# Project5.net
KiCad netlist of a schematic drawn in EasyEDA Pro
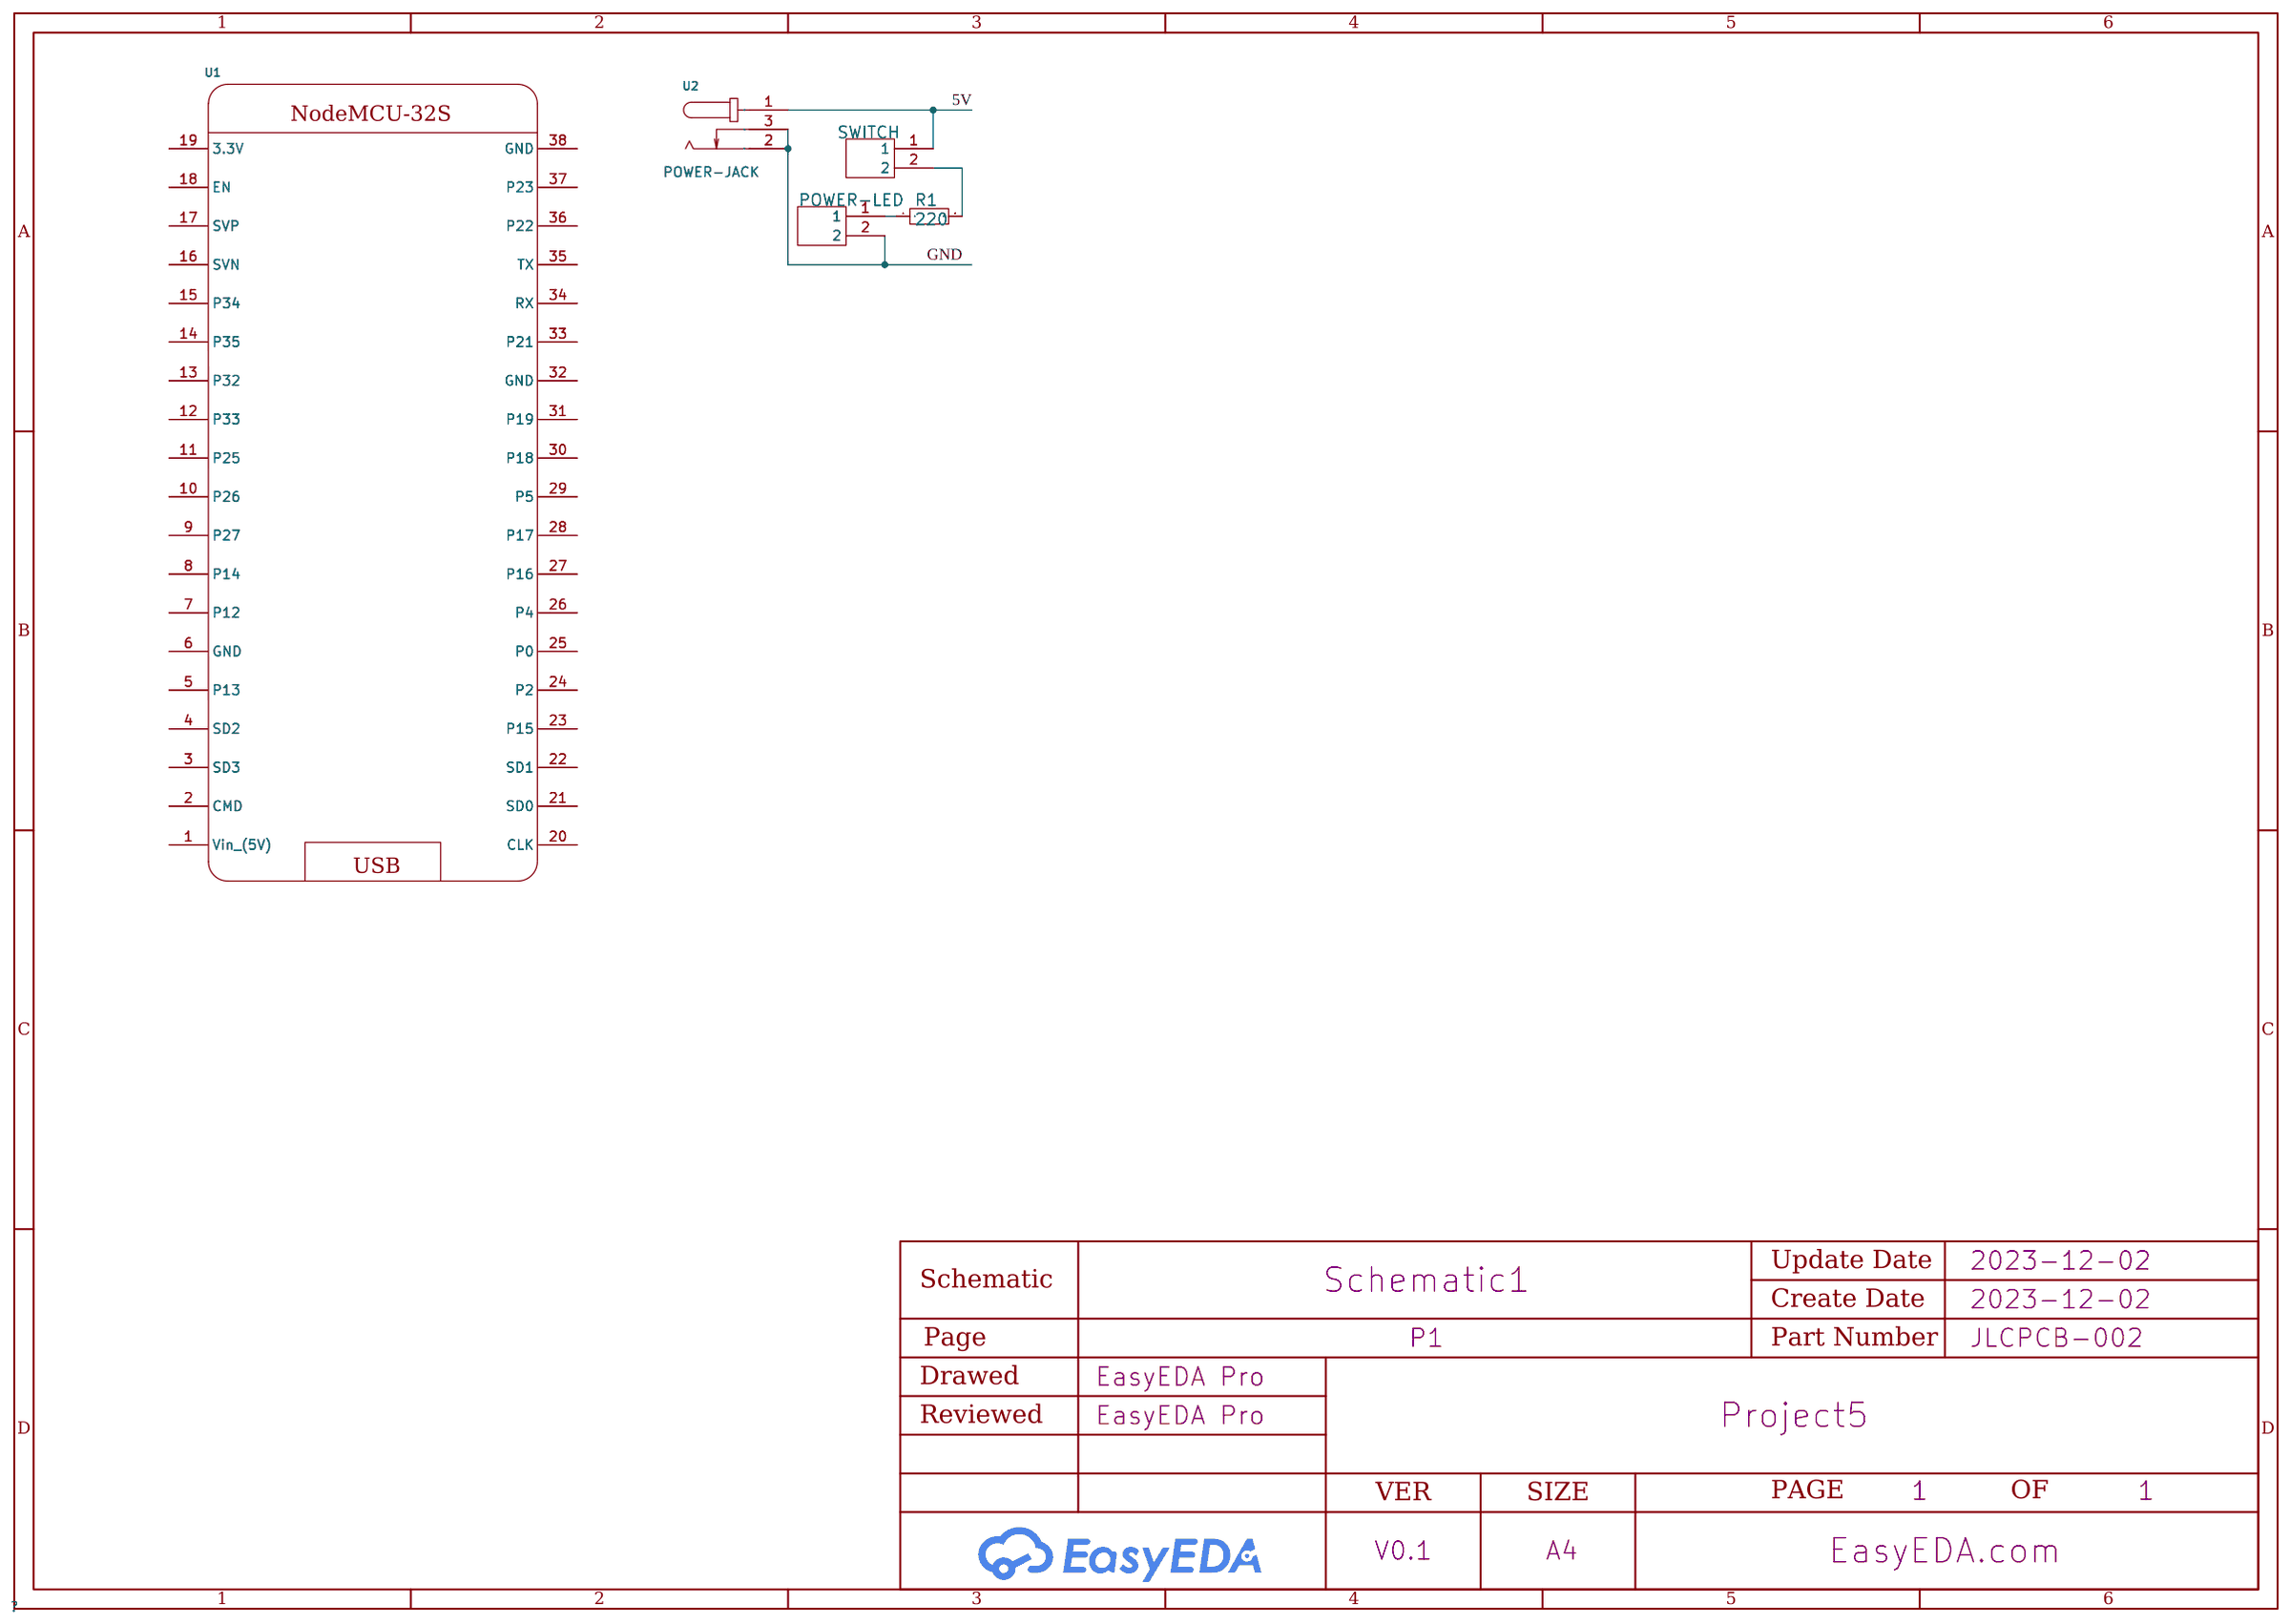
[diagram p0: schematic sheet]

(export (version "E")
  (design (tool "Eeschema 10.0.6"))
  (components
    (comp (ref "POWER-LED")
      (value "~")
      (footprint "easyedapro:JST 2.54-2PIN")
      (libsource (lib "easyedapro") (part "symbol_8d83"))
    )
    (comp (ref "R1")
      (value "220")
      (footprint "easyedapro:RES35")
      (fields
        (field (name "Manufacturer Part") "PTFR0805B130KN9")
        (field (name "Manufacturer") "ResistorToday")
      )
      (libsource (lib "easyedapro") (part "220"))
    )
    (comp (ref "SWITCH")
      (value "~")
      (footprint "easyedapro:JST 2.54-2PIN")
      (libsource (lib "easyedapro") (part "symbol_8d83"))
    )
    (comp (ref "U1")
      (value "~")
      (footprint "easyedapro:AI-THINKER_NODEMCU-32SLUA")
      (libsource (lib "easyedapro") (part "NODEMCU-ESP32"))
    )
    (comp (ref "U2")
      (value "POWER-JACK")
      (footprint "easyedapro:DC-IN-TH_POWER-JACK")
      (libsource (lib "easyedapro") (part "POWER-JACK"))
    )
  )
  (nets
    (net (code "1") (name "/5V") (class "Default")
      (node (ref "SWITCH") (pin "1") (pinfunction "1_1") (pintype "input"))
      (node (ref "U2") (pin "1") (pinfunction "1_1") (pintype "input"))
    )
    (net (code "2") (name "/GND") (class "Default")
      (node (ref "POWER-LED") (pin "2") (pinfunction "2_2") (pintype "input"))
      (node (ref "U2") (pin "2") (pinfunction "2_2") (pintype "input"))
      (node (ref "U2") (pin "3") (pinfunction "3_3") (pintype "input"))
    )
    (net (code "3") (name "Net-(POWER-LED-Pad1)") (class "Default")
      (node (ref "POWER-LED") (pin "1") (pinfunction "1_1") (pintype "input"))
      (node (ref "R1") (pin "1") (pinfunction "1_1") (pintype "input"))
    )
    (net (code "4") (name "Net-(R1-Pad2)") (class "Default")
      (node (ref "R1") (pin "2") (pinfunction "2_2") (pintype "input"))
      (node (ref "SWITCH") (pin "2") (pinfunction "2_2") (pintype "input"))
    )
    (net (code "5") (name "unconnected-(U1-3.3V-Pad19)") (class "Default")
      (node (ref "U1") (pin "19") (pinfunction "3.3V_19") (pintype "input"))
    )
    (net (code "6") (name "unconnected-(U1-CLK-Pad20)") (class "Default")
      (node (ref "U1") (pin "20") (pinfunction "CLK_20") (pintype "input"))
    )
    (net (code "7") (name "unconnected-(U1-CMD-Pad2)") (class "Default")
      (node (ref "U1") (pin "2") (pinfunction "CMD_2") (pintype "input"))
    )
    (net (code "8") (name "unconnected-(U1-EN-Pad18)") (class "Default")
      (node (ref "U1") (pin "18") (pinfunction "EN_18") (pintype "input"))
    )
    (net (code "9") (name "unconnected-(U1-GND-Pad6)") (class "Default")
      (node (ref "U1") (pin "6") (pinfunction "GND_6") (pintype "input"))
    )
    (net (code "10") (name "unconnected-(U1-GND-Pad32)") (class "Default")
      (node (ref "U1") (pin "32") (pinfunction "GND_32") (pintype "input"))
    )
    (net (code "11") (name "unconnected-(U1-GND-Pad38)") (class "Default")
      (node (ref "U1") (pin "38") (pinfunction "GND_38") (pintype "input"))
    )
    (net (code "12") (name "unconnected-(U1-P0-Pad25)") (class "Default")
      (node (ref "U1") (pin "25") (pinfunction "P0_25") (pintype "input"))
    )
    (net (code "13") (name "unconnected-(U1-P2-Pad24)") (class "Default")
      (node (ref "U1") (pin "24") (pinfunction "P2_24") (pintype "input"))
    )
    (net (code "14") (name "unconnected-(U1-P4-Pad26)") (class "Default")
      (node (ref "U1") (pin "26") (pinfunction "P4_26") (pintype "input"))
    )
    (net (code "15") (name "unconnected-(U1-P5-Pad29)") (class "Default")
      (node (ref "U1") (pin "29") (pinfunction "P5_29") (pintype "input"))
    )
    (net (code "16") (name "unconnected-(U1-P12-Pad7)") (class "Default")
      (node (ref "U1") (pin "7") (pinfunction "P12_7") (pintype "input"))
    )
    (net (code "17") (name "unconnected-(U1-P13-Pad5)") (class "Default")
      (node (ref "U1") (pin "5") (pinfunction "P13_5") (pintype "input"))
    )
    (net (code "18") (name "unconnected-(U1-P14-Pad8)") (class "Default")
      (node (ref "U1") (pin "8") (pinfunction "P14_8") (pintype "input"))
    )
    (net (code "19") (name "unconnected-(U1-P15-Pad23)") (class "Default")
      (node (ref "U1") (pin "23") (pinfunction "P15_23") (pintype "input"))
    )
    (net (code "20") (name "unconnected-(U1-P16-Pad27)") (class "Default")
      (node (ref "U1") (pin "27") (pinfunction "P16_27") (pintype "input"))
    )
    (net (code "21") (name "unconnected-(U1-P17-Pad28)") (class "Default")
      (node (ref "U1") (pin "28") (pinfunction "P17_28") (pintype "input"))
    )
    (net (code "22") (name "unconnected-(U1-P18-Pad30)") (class "Default")
      (node (ref "U1") (pin "30") (pinfunction "P18_30") (pintype "input"))
    )
    (net (code "23") (name "unconnected-(U1-P19-Pad31)") (class "Default")
      (node (ref "U1") (pin "31") (pinfunction "P19_31") (pintype "input"))
    )
    (net (code "24") (name "unconnected-(U1-P21-Pad33)") (class "Default")
      (node (ref "U1") (pin "33") (pinfunction "P21_33") (pintype "input"))
    )
    (net (code "25") (name "unconnected-(U1-P22-Pad36)") (class "Default")
      (node (ref "U1") (pin "36") (pinfunction "P22_36") (pintype "input"))
    )
    (net (code "26") (name "unconnected-(U1-P23-Pad37)") (class "Default")
      (node (ref "U1") (pin "37") (pinfunction "P23_37") (pintype "input"))
    )
    (net (code "27") (name "unconnected-(U1-P25-Pad11)") (class "Default")
      (node (ref "U1") (pin "11") (pinfunction "P25_11") (pintype "input"))
    )
    (net (code "28") (name "unconnected-(U1-P26-Pad10)") (class "Default")
      (node (ref "U1") (pin "10") (pinfunction "P26_10") (pintype "input"))
    )
    (net (code "29") (name "unconnected-(U1-P27-Pad9)") (class "Default")
      (node (ref "U1") (pin "9") (pinfunction "P27_9") (pintype "input"))
    )
    (net (code "30") (name "unconnected-(U1-P32-Pad13)") (class "Default")
      (node (ref "U1") (pin "13") (pinfunction "P32_13") (pintype "input"))
    )
    (net (code "31") (name "unconnected-(U1-P33-Pad12)") (class "Default")
      (node (ref "U1") (pin "12") (pinfunction "P33_12") (pintype "input"))
    )
    (net (code "32") (name "unconnected-(U1-P34-Pad15)") (class "Default")
      (node (ref "U1") (pin "15") (pinfunction "P34_15") (pintype "input"))
    )
    (net (code "33") (name "unconnected-(U1-P35-Pad14)") (class "Default")
      (node (ref "U1") (pin "14") (pinfunction "P35_14") (pintype "input"))
    )
    (net (code "34") (name "unconnected-(U1-RX-Pad34)") (class "Default")
      (node (ref "U1") (pin "34") (pinfunction "RX_34") (pintype "input"))
    )
    (net (code "35") (name "unconnected-(U1-SD0-Pad21)") (class "Default")
      (node (ref "U1") (pin "21") (pinfunction "SD0_21") (pintype "input"))
    )
    (net (code "36") (name "unconnected-(U1-SD1-Pad22)") (class "Default")
      (node (ref "U1") (pin "22") (pinfunction "SD1_22") (pintype "input"))
    )
    (net (code "37") (name "unconnected-(U1-SD2-Pad4)") (class "Default")
      (node (ref "U1") (pin "4") (pinfunction "SD2_4") (pintype "input"))
    )
    (net (code "38") (name "unconnected-(U1-SD3-Pad3)") (class "Default")
      (node (ref "U1") (pin "3") (pinfunction "SD3_3") (pintype "input"))
    )
    (net (code "39") (name "unconnected-(U1-SVN-Pad16)") (class "Default")
      (node (ref "U1") (pin "16") (pinfunction "SVN_16") (pintype "input"))
    )
    (net (code "40") (name "unconnected-(U1-SVP-Pad17)") (class "Default")
      (node (ref "U1") (pin "17") (pinfunction "SVP_17") (pintype "input"))
    )
    (net (code "41") (name "unconnected-(U1-TX-Pad35)") (class "Default")
      (node (ref "U1") (pin "35") (pinfunction "TX_35") (pintype "input"))
    )
    (net (code "42") (name "unconnected-(U1-Vin_(5V)-Pad1)") (class "Default")
      (node (ref "U1") (pin "1") (pinfunction "Vin_(5V)_1") (pintype "input"))
    )
  )
)
